# RN4020_BLE.net
KiCad netlist of a schematic drawn in EAGLE
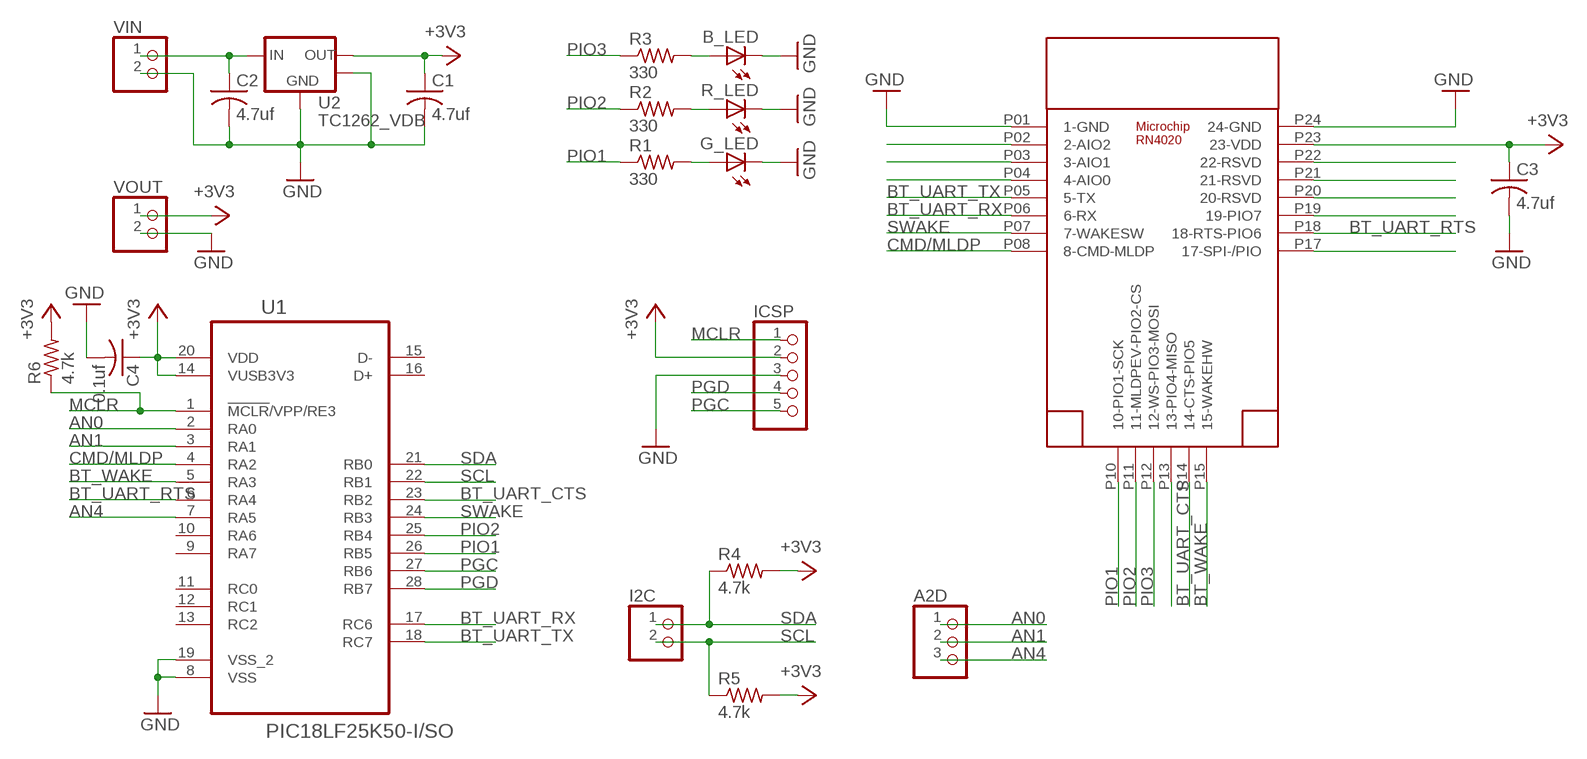
[diagram p0: schematic, sheet 1]

(export (version "E")
  (design (tool "Eeschema 10.0.6"))
  (components
    (comp (ref "A2D")
      (value "PINHD-1X3")
      (footprint "eagle-import:1X03")
      (libsource (lib "eagle-import") (part "PINHD-1X3"))
    )
    (comp (ref "B_LED")
      (value "LEDSMT1206")
      (footprint "eagle-import:1206")
      (libsource (lib "eagle-import") (part "LEDSMT1206"))
    )
    (comp (ref "C1")
      (value "4.7uf")
      (footprint "eagle-import:C1206")
      (libsource (lib "eagle-import") (part "C-USC1206"))
    )
    (comp (ref "C2")
      (value "4.7uf")
      (footprint "eagle-import:C1206")
      (libsource (lib "eagle-import") (part "C-USC1206"))
    )
    (comp (ref "C3")
      (value "4.7uf")
      (footprint "eagle-import:C1206")
      (libsource (lib "eagle-import") (part "C-USC1206"))
    )
    (comp (ref "C4")
      (value "0.1uf")
      (footprint "eagle-import:C1206")
      (libsource (lib "eagle-import") (part "C-USC1206"))
    )
    (comp (ref "G_LED")
      (value "LEDSMT1206")
      (footprint "eagle-import:1206")
      (libsource (lib "eagle-import") (part "LEDSMT1206"))
    )
    (comp (ref "I2C")
      (value "PINHD-1X2")
      (footprint "eagle-import:1X02")
      (libsource (lib "eagle-import") (part "PINHD-1X2"))
    )
    (comp (ref "ICSP")
      (value "PINHD-1X5")
      (footprint "eagle-import:1X05")
      (libsource (lib "eagle-import") (part "PINHD-1X5"))
    )
    (comp (ref "R1")
      (value "330")
      (footprint "eagle-import:R1206")
      (libsource (lib "eagle-import") (part "R-US_R1206"))
    )
    (comp (ref "R2")
      (value "330")
      (footprint "eagle-import:R1206")
      (libsource (lib "eagle-import") (part "R-US_R1206"))
    )
    (comp (ref "R3")
      (value "330")
      (footprint "eagle-import:R1206")
      (libsource (lib "eagle-import") (part "R-US_R1206"))
    )
    (comp (ref "R4")
      (value "4.7k")
      (footprint "eagle-import:R1206")
      (libsource (lib "eagle-import") (part "R-US_R1206"))
    )
    (comp (ref "R5")
      (value "4.7k")
      (footprint "eagle-import:R1206")
      (libsource (lib "eagle-import") (part "R-US_R1206"))
    )
    (comp (ref "R6")
      (value "4.7k")
      (footprint "eagle-import:R1206")
      (libsource (lib "eagle-import") (part "R-US_R1206"))
    )
    (comp (ref "R_LED")
      (value "LEDSMT1206")
      (footprint "eagle-import:1206")
      (libsource (lib "eagle-import") (part "LEDSMT1206"))
    )
    (comp (ref "U$1")
      (value "RN4020")
      (footprint "eagle-import:RN4020SMD")
      (libsource (lib "eagle-import") (part "RN4020"))
    )
    (comp (ref "U1")
      (value "PIC18LF25K50-I/SO")
      (footprint "eagle-import:SOIC127P1032X265-28N")
      (libsource (lib "eagle-import") (part "PIC18LF25K50-I/SO"))
    )
    (comp (ref "U2")
      (value "TC1262_VDB")
      (footprint "eagle-import:SOT-223-3")
      (libsource (lib "eagle-import") (part "TC1262_VDB"))
    )
    (comp (ref "VIN")
      (value "PINHD-1X2")
      (footprint "eagle-import:1X02")
      (libsource (lib "eagle-import") (part "PINHD-1X2"))
    )
    (comp (ref "VOUT")
      (value "PINHD-1X2")
      (footprint "eagle-import:1X02")
      (libsource (lib "eagle-import") (part "PINHD-1X2"))
    )
  )
  (nets
    (net (code "1") (name "+3V3") (class "Default")
      (node (ref "C1") (pin "1") (pinfunction "1_1") (pintype "passive"))
      (node (ref "C3") (pin "1") (pinfunction "1_1") (pintype "passive"))
      (node (ref "C4") (pin "1") (pinfunction "1_1") (pintype "passive"))
      (node (ref "ICSP") (pin "2") (pinfunction "2_2") (pintype "passive"))
      (node (ref "R4") (pin "2") (pinfunction "2_2") (pintype "passive"))
      (node (ref "R5") (pin "2") (pinfunction "2_2") (pintype "passive"))
      (node (ref "R6") (pin "2") (pinfunction "2_2") (pintype "passive"))
      (node (ref "U$1") (pin "P23") (pinfunction "23-VDD_P23") (pintype "bidirectional"))
      (node (ref "U1") (pin "14") (pinfunction "VUSB3V3_14") (pintype "power_in"))
      (node (ref "U1") (pin "20") (pinfunction "VDD_20") (pintype "power_in"))
      (node (ref "U2") (pin "3") (pinfunction "VOUT_3") (pintype "bidirectional"))
      (node (ref "VOUT") (pin "1") (pinfunction "1_1") (pintype "passive"))
    )
    (net (code "2") (name "/AN0") (class "Default")
      (node (ref "A2D") (pin "1") (pinfunction "1_1") (pintype "passive"))
      (node (ref "U1") (pin "2") (pinfunction "RA0_2") (pintype "bidirectional"))
    )
    (net (code "3") (name "/AN1") (class "Default")
      (node (ref "A2D") (pin "2") (pinfunction "2_2") (pintype "passive"))
      (node (ref "U1") (pin "3") (pinfunction "RA1_3") (pintype "bidirectional"))
    )
    (net (code "4") (name "/AN4") (class "Default")
      (node (ref "A2D") (pin "3") (pinfunction "3_3") (pintype "passive"))
      (node (ref "U1") (pin "7") (pinfunction "RA5_7") (pintype "bidirectional"))
    )
    (net (code "5") (name "/BT_UART_CTS") (class "Default")
      (node (ref "U$1") (pin "P14") (pinfunction "14-CTS-PIO5_P14") (pintype "bidirectional"))
      (node (ref "U1") (pin "23") (pinfunction "RB2_23") (pintype "bidirectional"))
    )
    (net (code "6") (name "/BT_UART_RTS") (class "Default")
      (node (ref "U$1") (pin "P18") (pinfunction "18-RTS-PIO6_P18") (pintype "bidirectional"))
      (node (ref "U1") (pin "6") (pinfunction "RA4_6") (pintype "bidirectional"))
    )
    (net (code "7") (name "/BT_UART_RX") (class "Default")
      (node (ref "U$1") (pin "P06") (pinfunction "6-RX_P06") (pintype "bidirectional"))
      (node (ref "U1") (pin "17") (pinfunction "RC6_17") (pintype "bidirectional"))
    )
    (net (code "8") (name "/BT_UART_TX") (class "Default")
      (node (ref "U$1") (pin "P05") (pinfunction "5-TX_P05") (pintype "bidirectional"))
      (node (ref "U1") (pin "18") (pinfunction "RC7_18") (pintype "bidirectional"))
    )
    (net (code "9") (name "/BT_WAKE") (class "Default")
      (node (ref "U$1") (pin "P15") (pinfunction "15-WAKEHW_P15") (pintype "bidirectional"))
      (node (ref "U1") (pin "5") (pinfunction "RA3_5") (pintype "bidirectional"))
    )
    (net (code "10") (name "/CMD{slash}MLDP") (class "Default")
      (node (ref "U$1") (pin "P08") (pinfunction "8-CMD-MLDP_P08") (pintype "bidirectional"))
      (node (ref "U1") (pin "4") (pinfunction "RA2_4") (pintype "bidirectional"))
    )
    (net (code "11") (name "/MCLR") (class "Default")
      (node (ref "ICSP") (pin "1") (pinfunction "1_1") (pintype "passive"))
      (node (ref "R6") (pin "1") (pinfunction "1_1") (pintype "passive"))
      (node (ref "U1") (pin "1") (pinfunction "~{MCLR}/VPP/RE3_1") (pintype "bidirectional"))
    )
    (net (code "12") (name "/PGC") (class "Default")
      (node (ref "ICSP") (pin "5") (pinfunction "5_5") (pintype "passive"))
      (node (ref "U1") (pin "27") (pinfunction "RB6_27") (pintype "bidirectional"))
    )
    (net (code "13") (name "/PGD") (class "Default")
      (node (ref "ICSP") (pin "4") (pinfunction "4_4") (pintype "passive"))
      (node (ref "U1") (pin "28") (pinfunction "RB7_28") (pintype "bidirectional"))
    )
    (net (code "14") (name "/PIO1") (class "Default")
      (node (ref "R1") (pin "1") (pinfunction "1_1") (pintype "passive"))
      (node (ref "U$1") (pin "P10") (pinfunction "10-PIO1-SCK_P10") (pintype "bidirectional"))
      (node (ref "U1") (pin "26") (pinfunction "RB5_26") (pintype "bidirectional"))
    )
    (net (code "15") (name "/PIO2") (class "Default")
      (node (ref "R2") (pin "1") (pinfunction "1_1") (pintype "passive"))
      (node (ref "U$1") (pin "P11") (pinfunction "11-MLDPEV-PIO2-CS_P11") (pintype "bidirectional"))
      (node (ref "U1") (pin "25") (pinfunction "RB4_25") (pintype "bidirectional"))
    )
    (net (code "16") (name "/PIO3") (class "Default")
      (node (ref "R3") (pin "1") (pinfunction "1_1") (pintype "passive"))
      (node (ref "U$1") (pin "P12") (pinfunction "12-WS-PIO3-MOSI_P12") (pintype "bidirectional"))
    )
    (net (code "17") (name "/SCL") (class "Default")
      (node (ref "I2C") (pin "2") (pinfunction "2_2") (pintype "passive"))
      (node (ref "R5") (pin "1") (pinfunction "1_1") (pintype "passive"))
      (node (ref "U1") (pin "22") (pinfunction "RB1_22") (pintype "bidirectional"))
    )
    (net (code "18") (name "/SDA") (class "Default")
      (node (ref "I2C") (pin "1") (pinfunction "1_1") (pintype "passive"))
      (node (ref "R4") (pin "1") (pinfunction "1_1") (pintype "passive"))
      (node (ref "U1") (pin "21") (pinfunction "RB0_21") (pintype "bidirectional"))
    )
    (net (code "19") (name "/SWAKE") (class "Default")
      (node (ref "U$1") (pin "P07") (pinfunction "7-WAKESW_P07") (pintype "bidirectional"))
      (node (ref "U1") (pin "24") (pinfunction "RB3_24") (pintype "bidirectional"))
    )
    (net (code "20") (name "GND") (class "Default")
      (node (ref "B_LED") (pin "C") (pinfunction "C_C") (pintype "passive"))
      (node (ref "C1") (pin "2") (pinfunction "2_2") (pintype "passive"))
      (node (ref "C2") (pin "2") (pinfunction "2_2") (pintype "passive"))
      (node (ref "C3") (pin "2") (pinfunction "2_2") (pintype "passive"))
      (node (ref "C4") (pin "2") (pinfunction "2_2") (pintype "passive"))
      (node (ref "G_LED") (pin "C") (pinfunction "C_C") (pintype "passive"))
      (node (ref "ICSP") (pin "3") (pinfunction "3_3") (pintype "passive"))
      (node (ref "R_LED") (pin "C") (pinfunction "C_C") (pintype "passive"))
      (node (ref "U$1") (pin "P01") (pinfunction "1-GND_P01") (pintype "bidirectional"))
      (node (ref "U$1") (pin "P24") (pinfunction "24-GND_P24") (pintype "bidirectional"))
      (node (ref "U1") (pin "19") (pinfunction "VSS_2_19") (pintype "power_in"))
      (node (ref "U1") (pin "8") (pinfunction "VSS_8") (pintype "power_in"))
      (node (ref "U2") (pin "2") (pinfunction "GND_2") (pintype "bidirectional"))
      (node (ref "U2") (pin "4") (pinfunction "TAB_4") (pintype "bidirectional"))
      (node (ref "VIN") (pin "2") (pinfunction "2_2") (pintype "passive"))
      (node (ref "VOUT") (pin "2") (pinfunction "2_2") (pintype "passive"))
    )
    (net (code "21") (name "Net-(B_LED-PadA)") (class "Default")
      (node (ref "B_LED") (pin "A") (pinfunction "A_A") (pintype "passive"))
      (node (ref "R3") (pin "2") (pinfunction "2_2") (pintype "passive"))
    )
    (net (code "22") (name "Net-(G_LED-PadA)") (class "Default")
      (node (ref "G_LED") (pin "A") (pinfunction "A_A") (pintype "passive"))
      (node (ref "R1") (pin "2") (pinfunction "2_2") (pintype "passive"))
    )
    (net (code "23") (name "Net-(R2-Pad2)") (class "Default")
      (node (ref "R2") (pin "2") (pinfunction "2_2") (pintype "passive"))
      (node (ref "R_LED") (pin "A") (pinfunction "A_A") (pintype "passive"))
    )
    (net (code "24") (name "Net-(U2-VIN)") (class "Default")
      (node (ref "C2") (pin "1") (pinfunction "1_1") (pintype "passive"))
      (node (ref "U2") (pin "1") (pinfunction "VIN_1") (pintype "bidirectional"))
      (node (ref "VIN") (pin "1") (pinfunction "1_1") (pintype "passive"))
    )
    (net (code "25") (name "unconnected-(U$1-2-AIO2-PadP02)") (class "Default")
      (node (ref "U$1") (pin "P02") (pinfunction "2-AIO2_P02") (pintype "bidirectional"))
    )
    (net (code "26") (name "unconnected-(U$1-3-AIO1-PadP03)") (class "Default")
      (node (ref "U$1") (pin "P03") (pinfunction "3-AIO1_P03") (pintype "bidirectional"))
    )
    (net (code "27") (name "unconnected-(U$1-4-AIO0-PadP04)") (class "Default")
      (node (ref "U$1") (pin "P04") (pinfunction "4-AIO0_P04") (pintype "bidirectional"))
    )
    (net (code "28") (name "unconnected-(U$1-13-PIO4-MISO-PadP13)") (class "Default")
      (node (ref "U$1") (pin "P13") (pinfunction "13-PIO4-MISO_P13") (pintype "bidirectional"))
    )
    (net (code "29") (name "unconnected-(U$1-17-SPI-{slash}PIO-PadP17)") (class "Default")
      (node (ref "U$1") (pin "P17") (pinfunction "17-SPI-/PIO_P17") (pintype "bidirectional"))
    )
    (net (code "30") (name "unconnected-(U$1-19-PIO7-PadP19)") (class "Default")
      (node (ref "U$1") (pin "P19") (pinfunction "19-PIO7_P19") (pintype "bidirectional"))
    )
    (net (code "31") (name "unconnected-(U$1-20-RSVD-PadP20)") (class "Default")
      (node (ref "U$1") (pin "P20") (pinfunction "20-RSVD_P20") (pintype "bidirectional"))
    )
    (net (code "32") (name "unconnected-(U$1-21-RSVD-PadP21)") (class "Default")
      (node (ref "U$1") (pin "P21") (pinfunction "21-RSVD_P21") (pintype "bidirectional"))
    )
    (net (code "33") (name "unconnected-(U$1-22-RSVD-PadP22)") (class "Default")
      (node (ref "U$1") (pin "P22") (pinfunction "22-RSVD_P22") (pintype "bidirectional"))
    )
    (net (code "34") (name "unconnected-(U1-D+-Pad16)") (class "Default")
      (node (ref "U1") (pin "16") (pinfunction "D+_16") (pintype "passive"))
    )
    (net (code "35") (name "unconnected-(U1-D--Pad15)") (class "Default")
      (node (ref "U1") (pin "15") (pinfunction "D-_15") (pintype "passive"))
    )
    (net (code "36") (name "unconnected-(U1-RA6-Pad10)") (class "Default")
      (node (ref "U1") (pin "10") (pinfunction "RA6_10") (pintype "bidirectional"))
    )
    (net (code "37") (name "unconnected-(U1-RA7-Pad9)") (class "Default")
      (node (ref "U1") (pin "9") (pinfunction "RA7_9") (pintype "bidirectional"))
    )
    (net (code "38") (name "unconnected-(U1-RC0-Pad11)") (class "Default")
      (node (ref "U1") (pin "11") (pinfunction "RC0_11") (pintype "bidirectional"))
    )
    (net (code "39") (name "unconnected-(U1-RC1-Pad12)") (class "Default")
      (node (ref "U1") (pin "12") (pinfunction "RC1_12") (pintype "bidirectional"))
    )
    (net (code "40") (name "unconnected-(U1-RC2-Pad13)") (class "Default")
      (node (ref "U1") (pin "13") (pinfunction "RC2_13") (pintype "bidirectional"))
    )
  )
)
